# cc2538.net
KiCad netlist of a schematic drawn in Altium Designer
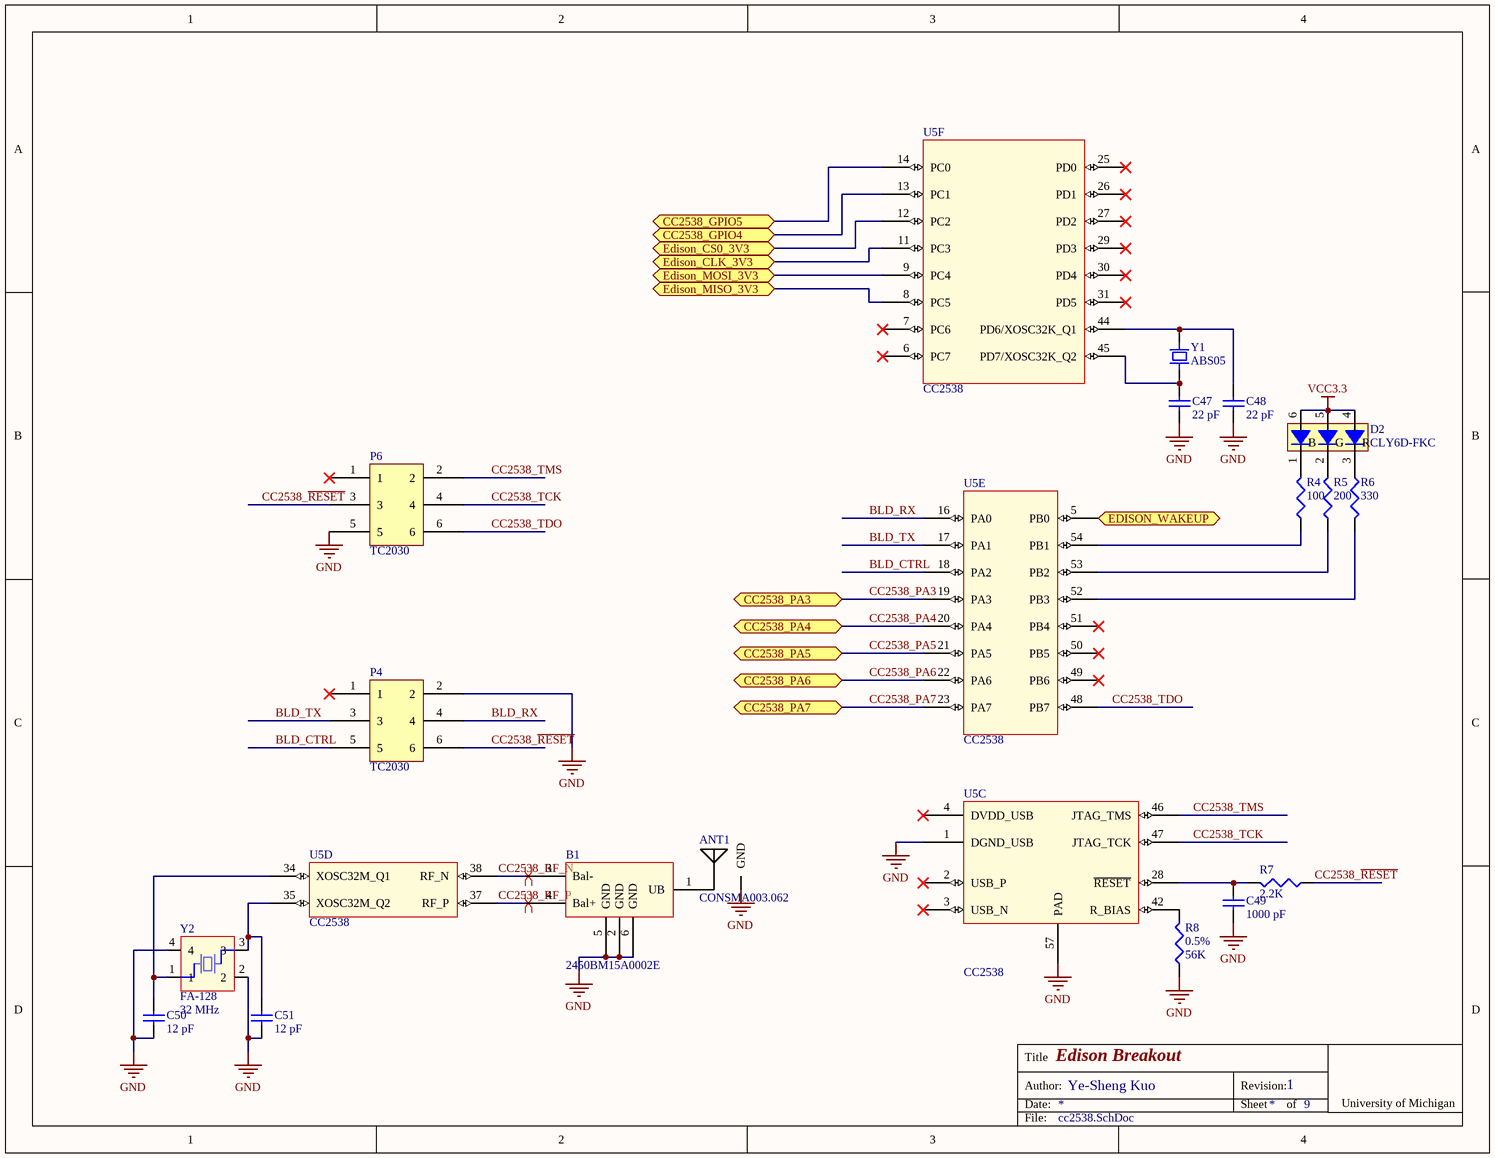
[diagram p0: cc2538.SchDoc]

(export (version "E")
  (design (tool "Eeschema 10.0.6"))
  (components
    (comp (ref "ANT1")
      (value "CONSMA003.062")
      (footprint "CONSMA003.062")
      (description "CONN SMA JACK 50 OHM EDGE MNT")
      (libsource (lib "RF") (part "CONSMA003.062"))
    )
    (comp (ref "B1")
      (value "2450BM15A0002E")
      (footprint "2450BM15A0002")
      (description "2.45 GHz Balun for TI CC253X")
      (libsource (lib "RF") (part "2450BM15A0002E"))
    )
    (comp (ref "C47")
      (value "22 pF")
      (footprint "0402")
      (description "Ceramic capacitor, 22 pF, 0402 package")
      (fields (field (name "TOLERANCE") "2%") (field (name "Comment") "Ceramic capacitor"))
      (libsource (lib "rlc") (part "C_22p_0402_ceramic"))
    )
    (comp (ref "C48")
      (value "22 pF")
      (footprint "0402")
      (description "Ceramic capacitor, 22 pF, 0402 package")
      (fields (field (name "TOLERANCE") "2%") (field (name "Comment") "Ceramic capacitor"))
      (libsource (lib "rlc") (part "C_22p_0402_ceramic"))
    )
    (comp (ref "C49")
      (value "1000 pF")
      (footprint "0402")
      (description "Ceramic capacitor, 1000 pF, 0402 package")
      (fields (field (name "TOLERANCE") "10%") (field (name "Comment") "Ceramic capacitor"))
      (libsource (lib "rlc") (part "C_1000p_50V_0402_ceramic"))
    )
    (comp (ref "C50")
      (value "12 pF")
      (footprint "0402")
      (description "Ceramic capacitor, 12 pF, 0402 package")
      (fields (field (name "TOLERANCE") "2%") (field (name "Comment") "Ceramic capacitor"))
      (libsource (lib "rlc") (part "C_12p_0402_ceramic"))
    )
    (comp (ref "C51")
      (value "12 pF")
      (footprint "0402")
      (description "Ceramic capacitor, 12 pF, 0402 package")
      (fields (field (name "TOLERANCE") "2%") (field (name "Comment") "Ceramic capacitor"))
      (libsource (lib "rlc") (part "C_12p_0402_ceramic"))
    )
    (comp (ref "D2")
      (value "CLY6D-FKC")
      (footprint "PLCC6")
      (description "CREE PLCC6 3 in 1 SMD LED")
      (libsource (lib "rlc") (part "D_CLY6D-FKC"))
    )
    (comp (ref "P4")
      (value "TC2030")
      (footprint "TC2030-IDC-NLFP")
      (description "TC2030-MCP-NL")
      (libsource (lib "connectors") (part "TC2030"))
    )
    (comp (ref "P6")
      (value "TC2030")
      (footprint "TC2030-IDC-NLFP")
      (description "TC2030-MCP-NL")
      (libsource (lib "connectors") (part "TC2030"))
    )
    (comp (ref "R4")
      (value "100")
      (footprint "0402")
      (description "Chip resistor, 100, 0402 package")
      (fields (field (name "TOLERANCE") "1%") (field (name "POWER") "1/16 W"))
      (libsource (lib "rlc") (part "R_100_0402"))
    )
    (comp (ref "R5")
      (value "200")
      (footprint "0402")
      (description "Chip resistor, 200, 0402 package")
      (fields (field (name "TOLERANCE") "1%") (field (name "POWER") "1/16 W"))
      (libsource (lib "rlc") (part "R_200_0402"))
    )
    (comp (ref "R6")
      (value "330")
      (footprint "0402")
      (description "Chip resistor, 330, 0402 package")
      (fields (field (name "TOLERANCE") "1%") (field (name "POWER") "1/16 W"))
      (libsource (lib "rlc") (part "R_330_0402"))
    )
    (comp (ref "R7")
      (value "2.2K")
      (footprint "0402")
      (description "Chip resistor, 2.2K, 0402 package")
      (fields (field (name "TOLERANCE") "1%") (field (name "POWER") "1/16 W"))
      (libsource (lib "rlc") (part "R_2.2K_0402"))
    )
    (comp (ref "R8")
      (value "56K")
      (footprint "0402")
      (description "Chip resistor, 56K, 0402 package")
      (fields
        (field (name "POWER") "1/16 W")
        (field (name "TOLERANCE") "0.5%")
        (field (name "Comment") "Chip resistor")
      )
      (libsource (lib "rlc") (part "R_56K_0402"))
    )
    (comp (ref "U5")
      (value "CC2538")
      (footprint "QFN56")
      (description "A Powerful System-On-Chip for 2.4-GHz IEEE 802.15.4, 6LoWPAN  and ZigBee Applications")
      (libsource (lib "mcu") (part "CC2538"))
    )
    (comp (ref "Y1")
      (value "ABS05")
      (footprint "ABS05")
      (description "32768 Hz SMD Low profile crystal")
      (libsource (lib "crystal_oscillators_rtc") (part "ABS05"))
    )
    (comp (ref "Y2")
      (value "FA-128")
      (footprint "FA-128")
      (description "MHz Range Crystal Unit")
      (fields (field (name "FREQUENCY") "32 MHz"))
      (libsource (lib "crystal_oscillators_rtc") (part "FA-128"))
    )
  )
  (nets
    (net (code "1") (name "/BLD_CTRL") (class "Default")
      (node (ref "P4") (pin "5") (pinfunction "5_5") (pintype "passive"))
      (node (ref "U5") (pin "18") (pinfunction "PA2_18") (pintype "bidirectional"))
    )
    (net (code "2") (name "/BLD_RX") (class "Default")
      (node (ref "P4") (pin "4") (pinfunction "4_4") (pintype "passive"))
      (node (ref "U5") (pin "16") (pinfunction "PA0_16") (pintype "bidirectional"))
    )
    (net (code "3") (name "/BLD_TX") (class "Default")
      (node (ref "P4") (pin "3") (pinfunction "3_3") (pintype "passive"))
      (node (ref "U5") (pin "17") (pinfunction "PA1_17") (pintype "bidirectional"))
    )
    (net (code "4") (name "/CC2538_GPIO4") (class "Default")
      (node (ref "U5") (pin "13") (pinfunction "PC1_13") (pintype "bidirectional"))
    )
    (net (code "5") (name "/CC2538_GPIO5") (class "Default")
      (node (ref "U5") (pin "14") (pinfunction "PC0_14") (pintype "bidirectional"))
    )
    (net (code "6") (name "/CC2538_PA3") (class "Default")
      (node (ref "U5") (pin "19") (pinfunction "PA3_19") (pintype "bidirectional"))
    )
    (net (code "7") (name "/CC2538_PA4") (class "Default")
      (node (ref "U5") (pin "20") (pinfunction "PA4_20") (pintype "bidirectional"))
    )
    (net (code "8") (name "/CC2538_PA5") (class "Default")
      (node (ref "U5") (pin "21") (pinfunction "PA5_21") (pintype "bidirectional"))
    )
    (net (code "9") (name "/CC2538_PA6") (class "Default")
      (node (ref "U5") (pin "22") (pinfunction "PA6_22") (pintype "bidirectional"))
    )
    (net (code "10") (name "/CC2538_PA7") (class "Default")
      (node (ref "U5") (pin "23") (pinfunction "PA7_23") (pintype "bidirectional"))
    )
    (net (code "11") (name "/CC2538_RF_N") (class "Default")
      (node (ref "B1") (pin "3") (pinfunction "Bal-_3") (pintype "passive"))
      (node (ref "U5") (pin "38") (pinfunction "RF_N_38") (pintype "bidirectional"))
    )
    (net (code "12") (name "/CC2538_RF_P") (class "Default")
      (node (ref "B1") (pin "4") (pinfunction "Bal+_4") (pintype "passive"))
      (node (ref "U5") (pin "37") (pinfunction "RF_P_37") (pintype "bidirectional"))
    )
    (net (code "13") (name "/CC2538_TCK") (class "Default")
      (node (ref "P6") (pin "4") (pinfunction "4_4") (pintype "passive"))
      (node (ref "U5") (pin "47") (pinfunction "JTAG_TCK_47") (pintype "bidirectional"))
    )
    (net (code "14") (name "/CC2538_TDO") (class "Default")
      (node (ref "P6") (pin "6") (pinfunction "6_6") (pintype "passive"))
      (node (ref "U5") (pin "48") (pinfunction "PB7_48") (pintype "bidirectional"))
    )
    (net (code "15") (name "/CC2538_TMS") (class "Default")
      (node (ref "P6") (pin "2") (pinfunction "2_2") (pintype "passive"))
      (node (ref "U5") (pin "46") (pinfunction "JTAG_TMS_46") (pintype "bidirectional"))
    )
    (net (code "16") (name "/CC2538_~{RESET}") (class "Default")
      (node (ref "P4") (pin "6") (pinfunction "6_6") (pintype "passive"))
      (node (ref "P6") (pin "3") (pinfunction "3_3") (pintype "passive"))
      (node (ref "R7") (pin "2") (pintype "passive"))
    )
    (net (code "17") (name "/EDISON_WAKEUP") (class "Default")
      (node (ref "U5") (pin "5") (pinfunction "PB0_5") (pintype "bidirectional"))
    )
    (net (code "18") (name "/Edison_CLK_3V3") (class "Default")
      (node (ref "U5") (pin "11") (pinfunction "PC3_11") (pintype "bidirectional"))
    )
    (net (code "19") (name "/Edison_CS0_3V3") (class "Default")
      (node (ref "U5") (pin "12") (pinfunction "PC2_12") (pintype "bidirectional"))
    )
    (net (code "20") (name "/Edison_MISO_3V3") (class "Default")
      (node (ref "U5") (pin "8") (pinfunction "PC5_8") (pintype "bidirectional"))
    )
    (net (code "21") (name "/Edison_MOSI_3V3") (class "Default")
      (node (ref "U5") (pin "9") (pinfunction "PC4_9") (pintype "bidirectional"))
    )
    (net (code "22") (name "GND") (class "Default")
      (node (ref "ANT1") (pin "1") (pinfunction "GND_1") (pintype "power_in"))
      (node (ref "B1") (pin "2") (pinfunction "GND_2") (pintype "passive"))
      (node (ref "B1") (pin "5") (pinfunction "GND_5") (pintype "passive"))
      (node (ref "B1") (pin "6") (pinfunction "GND_6") (pintype "passive"))
      (node (ref "C47") (pin "2") (pintype "passive"))
      (node (ref "C48") (pin "2") (pintype "passive"))
      (node (ref "C49") (pin "2") (pintype "passive"))
      (node (ref "C50") (pin "1") (pintype "passive"))
      (node (ref "C51") (pin "1") (pintype "passive"))
      (node (ref "P4") (pin "2") (pinfunction "2_2") (pintype "passive"))
      (node (ref "P6") (pin "5") (pinfunction "5_5") (pintype "passive"))
      (node (ref "R8") (pin "2") (pintype "passive"))
      (node (ref "U5") (pin "1") (pinfunction "DGND_USB_1") (pintype "power_in"))
      (node (ref "U5") (pin "57") (pinfunction "PAD_57") (pintype "power_in"))
      (node (ref "Y2") (pin "2") (pinfunction "2_2") (pintype "passive"))
      (node (ref "Y2") (pin "4") (pinfunction "4_4") (pintype "passive"))
    )
    (net (code "23") (name "Net-(B1-UB)") (class "Default")
      (node (ref "ANT1") (pin "2") (pintype "passive"))
      (node (ref "B1") (pin "1") (pinfunction "UB_1") (pintype "passive"))
    )
    (net (code "24") (name "Net-(D2-Pad1)") (class "Default")
      (node (ref "D2") (pin "1") (pintype "passive"))
      (node (ref "R4") (pin "1") (pintype "passive"))
    )
    (net (code "25") (name "Net-(D2-Pad2)") (class "Default")
      (node (ref "D2") (pin "2") (pintype "passive"))
      (node (ref "R5") (pin "1") (pintype "passive"))
    )
    (net (code "26") (name "Net-(D2-Pad3)") (class "Default")
      (node (ref "D2") (pin "3") (pinfunction "3_3") (pintype "passive"))
      (node (ref "R6") (pin "2") (pintype "passive"))
    )
    (net (code "27") (name "Net-(U5C-R_BIAS)") (class "Default")
      (node (ref "R8") (pin "1") (pintype "passive"))
      (node (ref "U5") (pin "42") (pinfunction "R_BIAS_42") (pintype "bidirectional"))
    )
    (net (code "28") (name "Net-(U5C-~{RESET})") (class "Default")
      (node (ref "C49") (pin "1") (pintype "passive"))
      (node (ref "R7") (pin "1") (pintype "passive"))
      (node (ref "U5") (pin "28") (pinfunction "~{RESET}_28") (pintype "bidirectional"))
    )
    (net (code "29") (name "Net-(U5D-XOSC32M_Q1)") (class "Default")
      (node (ref "C50") (pin "2") (pintype "passive"))
      (node (ref "U5") (pin "34") (pinfunction "XOSC32M_Q1_34") (pintype "bidirectional"))
      (node (ref "Y2") (pin "1") (pinfunction "1_1") (pintype "passive"))
    )
    (net (code "30") (name "Net-(U5D-XOSC32M_Q2)") (class "Default")
      (node (ref "C51") (pin "2") (pintype "passive"))
      (node (ref "U5") (pin "35") (pinfunction "XOSC32M_Q2_35") (pintype "bidirectional"))
      (node (ref "Y2") (pin "3") (pinfunction "3_3") (pintype "passive"))
    )
    (net (code "31") (name "Net-(U5E-PB1)") (class "Default")
      (node (ref "R4") (pin "2") (pintype "passive"))
      (node (ref "U5") (pin "54") (pinfunction "PB1_54") (pintype "bidirectional"))
    )
    (net (code "32") (name "Net-(U5E-PB2)") (class "Default")
      (node (ref "R5") (pin "2") (pintype "passive"))
      (node (ref "U5") (pin "53") (pinfunction "PB2_53") (pintype "bidirectional"))
    )
    (net (code "33") (name "Net-(U5E-PB3)") (class "Default")
      (node (ref "R6") (pin "1") (pintype "passive"))
      (node (ref "U5") (pin "52") (pinfunction "PB3_52") (pintype "bidirectional"))
    )
    (net (code "34") (name "Net-(U5F-PD6{slash}XOSC32K_Q1)") (class "Default")
      (node (ref "C48") (pin "1") (pintype "passive"))
      (node (ref "U5") (pin "44") (pinfunction "PD6/XOSC32K_Q1_44") (pintype "bidirectional"))
      (node (ref "Y1") (pin "1") (pintype "passive"))
    )
    (net (code "35") (name "Net-(U5F-PD7{slash}XOSC32K_Q2)") (class "Default")
      (node (ref "C47") (pin "1") (pintype "passive"))
      (node (ref "U5") (pin "45") (pinfunction "PD7/XOSC32K_Q2_45") (pintype "bidirectional"))
      (node (ref "Y1") (pin "2") (pintype "passive"))
    )
    (net (code "36") (name "VCC3.3") (class "Default")
      (node (ref "D2") (pin "4") (pinfunction "4_4") (pintype "passive"))
      (node (ref "D2") (pin "5") (pinfunction "5_5") (pintype "passive"))
      (node (ref "D2") (pin "6") (pinfunction "6_6") (pintype "passive"))
    )
    (net (code "37") (name "unconnected-(P4-Pad1)") (class "Default")
      (node (ref "P4") (pin "1") (pinfunction "1_1") (pintype "passive+no_connect"))
    )
    (net (code "38") (name "unconnected-(P6-Pad1)") (class "Default")
      (node (ref "P6") (pin "1") (pinfunction "1_1") (pintype "passive+no_connect"))
    )
    (net (code "39") (name "unconnected-(U5C-DVDD_USB-Pad4)") (class "Default")
      (node (ref "U5") (pin "4") (pinfunction "DVDD_USB_4") (pintype "power_in+no_connect"))
    )
    (net (code "40") (name "unconnected-(U5C-USB_N-Pad3)") (class "Default")
      (node (ref "U5") (pin "3") (pinfunction "USB_N_3") (pintype "bidirectional+no_connect"))
    )
    (net (code "41") (name "unconnected-(U5C-USB_P-Pad2)") (class "Default")
      (node (ref "U5") (pin "2") (pinfunction "USB_P_2") (pintype "bidirectional+no_connect"))
    )
    (net (code "42") (name "unconnected-(U5E-PB4-Pad51)") (class "Default")
      (node (ref "U5") (pin "51") (pinfunction "PB4_51") (pintype "bidirectional+no_connect"))
    )
    (net (code "43") (name "unconnected-(U5E-PB5-Pad50)") (class "Default")
      (node (ref "U5") (pin "50") (pinfunction "PB5_50") (pintype "bidirectional+no_connect"))
    )
    (net (code "44") (name "unconnected-(U5E-PB6-Pad49)") (class "Default")
      (node (ref "U5") (pin "49") (pinfunction "PB6_49") (pintype "bidirectional+no_connect"))
    )
    (net (code "45") (name "unconnected-(U5F-PC6-Pad7)") (class "Default")
      (node (ref "U5") (pin "7") (pinfunction "PC6_7") (pintype "bidirectional+no_connect"))
    )
    (net (code "46") (name "unconnected-(U5F-PC7-Pad6)") (class "Default")
      (node (ref "U5") (pin "6") (pinfunction "PC7_6") (pintype "bidirectional+no_connect"))
    )
    (net (code "47") (name "unconnected-(U5F-PD0-Pad25)") (class "Default")
      (node (ref "U5") (pin "25") (pinfunction "PD0_25") (pintype "bidirectional+no_connect"))
    )
    (net (code "48") (name "unconnected-(U5F-PD1-Pad26)") (class "Default")
      (node (ref "U5") (pin "26") (pinfunction "PD1_26") (pintype "bidirectional+no_connect"))
    )
    (net (code "49") (name "unconnected-(U5F-PD2-Pad27)") (class "Default")
      (node (ref "U5") (pin "27") (pinfunction "PD2_27") (pintype "bidirectional+no_connect"))
    )
    (net (code "50") (name "unconnected-(U5F-PD3-Pad29)") (class "Default")
      (node (ref "U5") (pin "29") (pinfunction "PD3_29") (pintype "bidirectional+no_connect"))
    )
    (net (code "51") (name "unconnected-(U5F-PD4-Pad30)") (class "Default")
      (node (ref "U5") (pin "30") (pinfunction "PD4_30") (pintype "bidirectional+no_connect"))
    )
    (net (code "52") (name "unconnected-(U5F-PD5-Pad31)") (class "Default")
      (node (ref "U5") (pin "31") (pinfunction "PD5_31") (pintype "bidirectional+no_connect"))
    )
  )
)
